# GSM.net
KiCad netlist of a schematic drawn in Altium Designer
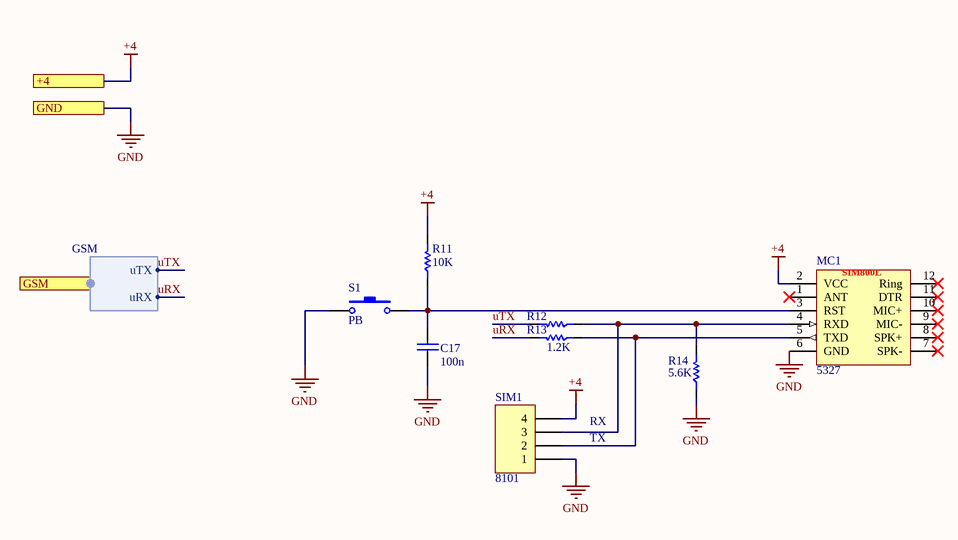
[diagram p0: GSM.SchDoc]

(export (version "E")
  (design (tool "Eeschema 10.0.6"))
  (components
    (comp (ref "C17")
      (value "100n")
      (footprint "CAP 1206/3216")
      (description "Bipolar ceramic capacitor SMD")
      (fields (field (name "VALIDATION") "Valid"))
      (libsource (lib "aKaReZa") (part "Cap_Multi_SMD_100nF_1206"))
    )
    (comp (ref "MC1")
      (value "Sim800L")
      (footprint "Sim800L_Module")
      (description "SimCom GSM/GPRS Module")
      (fields (field (name "INFLOW") "5327") (field (name "VALIDATION") "NT"))
      (libsource (lib "aKaReZa") (part "ModSen_Com_Sim800L"))
    )
    (comp (ref "R11")
      (value "10K")
      (footprint "RES 1206 (3216X08L)")
      (description "Resistor")
      (fields (field (name "VALIDATION") "Valid"))
      (libsource (lib "aKaReZa") (part "Res_SMD_1206"))
    )
    (comp (ref "R12")
      (value "47K")
      (footprint "RES 1206 (3216X08L)")
      (description "Resistor")
      (fields (field (name "VALIDATION") "Valid"))
      (libsource (lib "aKaReZa") (part "Res_SMD_1206"))
    )
    (comp (ref "R13")
      (value "1.2K")
      (footprint "RES 1206 (3216X08L)")
      (description "Resistor")
      (fields (field (name "Comment") "1K") (field (name "VALIDATION") "Valid"))
      (libsource (lib "aKaReZa") (part "Res_SMD_1206"))
    )
    (comp (ref "R14")
      (value "5.6K")
      (footprint "RES 1206 (3216X08L)")
      (description "Resistor")
      (fields (field (name "VALIDATION") "Valid"))
      (libsource (lib "aKaReZa") (part "Res_SMD_1206"))
    )
    (comp (ref "S1")
      (value "PB")
      (footprint "SW_PB_SMD_2PIN_SPST_6X3X2")
      (description "SMT Tactile ‎Switch")
      (fields (field (name "VALIDATION") "Valid"))
      (libsource (lib "aKaReZa") (part "SW_PushButton_2_SMD"))
    )
    (comp (ref "SIM1")
      (value "4")
      (footprint "HDR_THT_4F_2.54mm")
      (description "Header, single row, 4 pin")
      (fields (field (name "INFLOW") "8101") (field (name "VALIDATION") "NT"))
      (libsource (lib "aKaReZa") (part "Con_FPH_4x1_V_THT_2.54"))
    )
  )
  (nets
    (net (code "2") (name "+4") (class "Default")
      (node (ref "MC1") (pin "2") (pinfunction "VCC_2") (pintype "power_in"))
      (node (ref "R11") (pin "2") (pinfunction "2_2") (pintype "passive"))
      (node (ref "SIM1") (pin "4") (pinfunction "4_4") (pintype "passive"))
    )
    (net (code "3") (name "/uRX") (class "Default")
      (node (ref "R13") (pin "2") (pinfunction "2_2") (pintype "passive"))
    )
    (net (code "4") (name "/uTX") (class "Default")
      (node (ref "R12") (pin "2") (pinfunction "2_2") (pintype "passive"))
    )
    (net (code "6") (name "GND") (class "Default")
      (node (ref "C17") (pin "2") (pinfunction "2_2") (pintype "passive"))
      (node (ref "MC1") (pin "6") (pinfunction "GND_6") (pintype "power_in"))
      (node (ref "R14") (pin "1") (pinfunction "1_1") (pintype "passive"))
      (node (ref "S1") (pin "2") (pinfunction "2_2") (pintype "passive"))
      (node (ref "SIM1") (pin "1") (pinfunction "1_1") (pintype "passive"))
    )
    (net (code "7") (name "Net-(MC1-RST)") (class "Default")
      (node (ref "C17") (pin "1") (pinfunction "1_1") (pintype "passive"))
      (node (ref "MC1") (pin "3") (pinfunction "RST_3") (pintype "passive"))
      (node (ref "R11") (pin "1") (pinfunction "1_1") (pintype "passive"))
      (node (ref "S1") (pin "1") (pinfunction "1_1") (pintype "passive"))
    )
    (net (code "8") (name "Net-(MC1-RXD)") (class "Default")
      (node (ref "MC1") (pin "4") (pinfunction "RXD_4") (pintype "input"))
      (node (ref "R12") (pin "1") (pinfunction "1_1") (pintype "passive"))
      (node (ref "R14") (pin "2") (pinfunction "2_2") (pintype "passive"))
      (node (ref "SIM1") (pin "3") (pinfunction "3_3") (pintype "passive"))
    )
    (net (code "9") (name "Net-(MC1-TXD)") (class "Default")
      (node (ref "MC1") (pin "5") (pinfunction "TXD_5") (pintype "output"))
      (node (ref "R13") (pin "1") (pinfunction "1_1") (pintype "passive"))
      (node (ref "SIM1") (pin "2") (pinfunction "2_2") (pintype "passive"))
    )
    (net (code "10") (name "unconnected-(MC1-ANT-Pad1)") (class "Default")
      (node (ref "MC1") (pin "1") (pinfunction "ANT_1") (pintype "passive+no_connect"))
    )
    (net (code "11") (name "unconnected-(MC1-DTR-Pad11)") (class "Default")
      (node (ref "MC1") (pin "11") (pinfunction "DTR_11") (pintype "passive+no_connect"))
    )
    (net (code "12") (name "unconnected-(MC1-MIC+-Pad10)") (class "Default")
      (node (ref "MC1") (pin "10") (pinfunction "MIC+_10") (pintype "passive+no_connect"))
    )
    (net (code "13") (name "unconnected-(MC1-MIC--Pad9)") (class "Default")
      (node (ref "MC1") (pin "9") (pinfunction "MIC-_9") (pintype "passive+no_connect"))
    )
    (net (code "14") (name "unconnected-(MC1-Ring-Pad12)") (class "Default")
      (node (ref "MC1") (pin "12") (pinfunction "Ring_12") (pintype "passive+no_connect"))
    )
    (net (code "15") (name "unconnected-(MC1-SPK+-Pad8)") (class "Default")
      (node (ref "MC1") (pin "8") (pinfunction "SPK+_8") (pintype "passive+no_connect"))
    )
    (net (code "16") (name "unconnected-(MC1-SPK--Pad7)") (class "Default")
      (node (ref "MC1") (pin "7") (pinfunction "SPK-_7") (pintype "passive+no_connect"))
    )
  )
)
